# MonitorAndMCUConn.net
KiCad netlist of a schematic drawn in Altium Designer
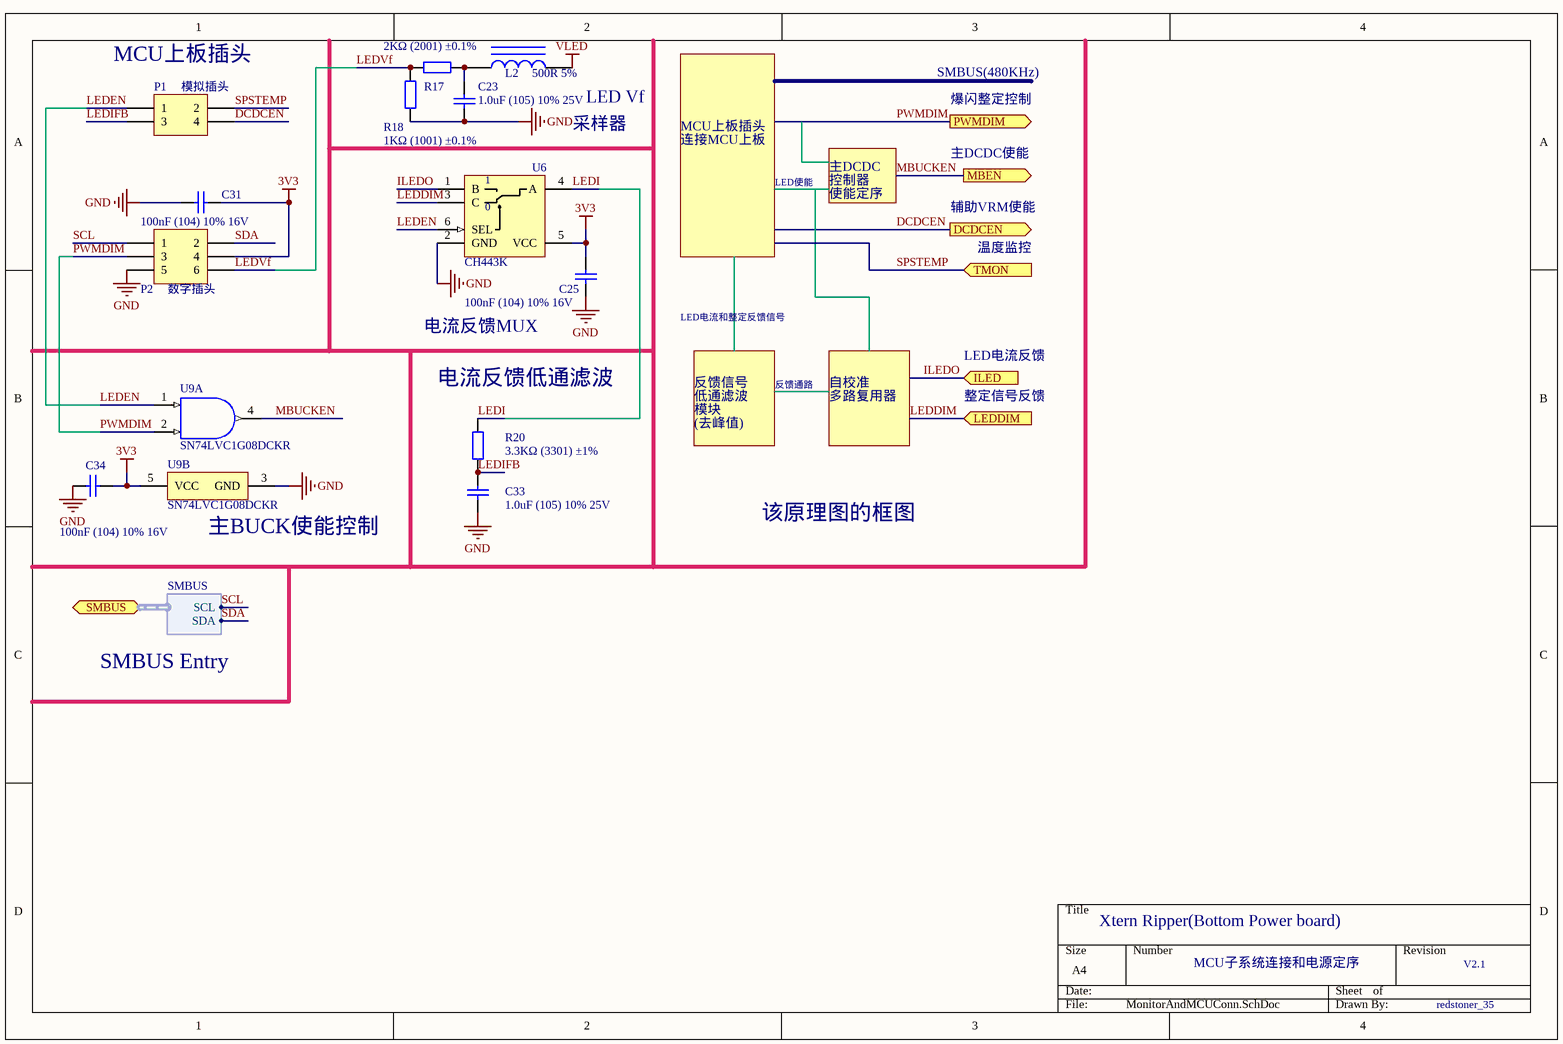
[diagram p0: MonitorAndMCUConn.SchDoc]

(export (version "E")
  (design (tool "Eeschema 10.0.6"))
  (components
    (comp (ref "C23")
      (value "1.0uF (105) 10% 25V")
      (footprint "0402_C")
      (description "贴片电容")
      (libsource (lib "Miscellaneous Devices LC") (part "0402 1.0uF (105) 10% 25V"))
    )
    (comp (ref "C25")
      (value "100nF (104) 10% 16V")
      (footprint "0402_C")
      (description "贴片电容")
      (libsource (lib "Miscellaneous Devices LC") (part "0402 100nF (104) 10% 16V"))
    )
    (comp (ref "C31")
      (value "100nF (104) 10% 16V")
      (footprint "0402_C")
      (description "贴片电容")
      (libsource (lib "Miscellaneous Devices LC") (part "0402 100nF (104) 10% 16V"))
    )
    (comp (ref "C33")
      (value "1.0uF (105) 10% 25V")
      (footprint "0402_C")
      (description "贴片电容")
      (libsource (lib "Miscellaneous Devices LC") (part "0402 1.0uF (105) 10% 25V"))
    )
    (comp (ref "C34")
      (value "100nF (104) 10% 16V")
      (footprint "0402_C")
      (description "贴片电容")
      (libsource (lib "Miscellaneous Devices LC") (part "0402 100nF (104) 10% 16V"))
    )
    (comp (ref "L2")
      (value "500R 5%")
      (footprint "0402_L")
      (description "贴片磁珠")
      (libsource (lib "Miscellaneous Devices LC") (part "0402 27nH 5%"))
    )
    (comp (ref "P1")
      (value "模拟插头")
      (footprint "MHDR2X2")
      (description "Header, 2-Pin, Dual row")
      (fields (field (name "PUBLISHER") "Altium Limited"))
      (libsource (lib "Miscellaneous Connectors") (part "MHDR2X2"))
    )
    (comp (ref "P2")
      (value "数字插头")
      (footprint "MHDR2X3")
      (description "Header, 3-Pin, Dual row")
      (fields (field (name "PUBLISHER") "Altium Limited"))
      (libsource (lib "Miscellaneous Connectors") (part "MHDR2X3"))
    )
    (comp (ref "R17")
      (value "2KΩ (2001) ±0.1%")
      (footprint "0402_R")
      (description "贴片电阻")
      (libsource (lib "Miscellaneous Devices LC") (part "0402 2KΩ (2001) 1%"))
    )
    (comp (ref "R18")
      (value "1KΩ (1001) ±0.1%")
      (footprint "0402_R")
      (description "贴片电阻")
      (libsource (lib "Miscellaneous Devices LC") (part "0402 1KΩ (1001) 1%"))
    )
    (comp (ref "R20")
      (value "3.3KΩ (3301) ±1%")
      (footprint "0402_R")
      (description "贴片电阻")
      (libsource (lib "Miscellaneous Devices LC") (part "0402 3.3KΩ (3301) 1%"))
    )
    (comp (ref "U6")
      (value "CH443K")
      (footprint "SC70-6")
      (description "Low-Voltage Analog Switch SPDT,1.8-5V Power")
      (libsource (lib "custom") (part "NC7SB3157P6X"))
    )
    (comp (ref "U9")
      (value "SN74LVC1G08DCKR")
      (footprint "DCK0005A_N")
      (description "Single 2-Input Positive-AND Gate, DCK0005A, LARGE T&R")
      (fields
        (field (name "GENERIC PART NUMBER") "SN74LVC1G08")
        (field (name "MANUFACTURER") "Texas Instruments")
      )
      (libsource (lib "TI_Logic_Little_Logic") (part "SN74LVC1G08DCKR"))
    )
  )
  (nets
    (net (code "2") (name "/DCDCEN") (class "Default")
      (node (ref "P1") (pin "4") (pinfunction "4_4") (pintype "passive"))
    )
    (net (code "3") (name "/ILEDO") (class "Default")
      (node (ref "U6") (pin "1") (pinfunction "B_1") (pintype "passive"))
    )
    (net (code "4") (name "/LEDDIM") (class "Default")
      (node (ref "U6") (pin "3") (pinfunction "C_3") (pintype "passive"))
    )
    (net (code "5") (name "/LEDEN") (class "Default")
      (node (ref "P1") (pin "1") (pinfunction "1_1") (pintype "passive"))
      (node (ref "U6") (pin "6") (pinfunction "SEL_6") (pintype "input"))
      (node (ref "U9") (pin "1") (pinfunction "A_1") (pintype "input"))
    )
    (net (code "6") (name "/LEDI") (class "Default")
      (node (ref "R20") (pin "2") (pinfunction "2_2") (pintype "passive"))
      (node (ref "U6") (pin "4") (pinfunction "A_4") (pintype "passive"))
    )
    (net (code "7") (name "/LEDIFB") (class "Default")
      (node (ref "C33") (pin "2") (pinfunction "2_2") (pintype "passive"))
      (node (ref "P1") (pin "3") (pinfunction "3_3") (pintype "passive"))
      (node (ref "R20") (pin "1") (pinfunction "1_1") (pintype "passive"))
    )
    (net (code "8") (name "/LEDVf") (class "Default")
      (node (ref "P2") (pin "6") (pinfunction "6_6") (pintype "passive"))
      (node (ref "R17") (pin "2") (pinfunction "2_2") (pintype "passive"))
      (node (ref "R18") (pin "2") (pinfunction "2_2") (pintype "passive"))
    )
    (net (code "9") (name "/MBUCKEN") (class "Default")
      (node (ref "U9") (pin "4") (pinfunction "Y_4") (pintype "output"))
    )
    (net (code "10") (name "/PWMDIM") (class "Default")
      (node (ref "P2") (pin "3") (pinfunction "3_3") (pintype "passive"))
      (node (ref "U9") (pin "2") (pinfunction "B_2") (pintype "input"))
    )
    (net (code "11") (name "/SCL") (class "Default")
      (node (ref "P2") (pin "1") (pinfunction "1_1") (pintype "passive"))
    )
    (net (code "12") (name "/SDA") (class "Default")
      (node (ref "P2") (pin "2") (pinfunction "2_2") (pintype "passive"))
    )
    (net (code "13") (name "/SPSTEMP") (class "Default")
      (node (ref "P1") (pin "2") (pinfunction "2_2") (pintype "passive"))
    )
    (net (code "15") (name "3V3") (class "Default")
      (node (ref "C25") (pin "2") (pinfunction "2_2") (pintype "passive"))
      (node (ref "C31") (pin "2") (pinfunction "2_2") (pintype "passive"))
      (node (ref "C34") (pin "2") (pinfunction "2_2") (pintype "passive"))
      (node (ref "P2") (pin "4") (pinfunction "4_4") (pintype "passive"))
      (node (ref "U6") (pin "5") (pinfunction "VCC_5") (pintype "power_in"))
      (node (ref "U9") (pin "5") (pinfunction "VCC_5") (pintype "power_in"))
    )
    (net (code "16") (name "GND") (class "Default")
      (node (ref "C23") (pin "1") (pinfunction "1_1") (pintype "passive"))
      (node (ref "C25") (pin "1") (pinfunction "1_1") (pintype "passive"))
      (node (ref "C31") (pin "1") (pinfunction "1_1") (pintype "passive"))
      (node (ref "C33") (pin "1") (pinfunction "1_1") (pintype "passive"))
      (node (ref "C34") (pin "1") (pinfunction "1_1") (pintype "passive"))
      (node (ref "P2") (pin "5") (pinfunction "5_5") (pintype "passive"))
      (node (ref "R18") (pin "1") (pinfunction "1_1") (pintype "passive"))
      (node (ref "U6") (pin "2") (pinfunction "GND_2") (pintype "power_in"))
      (node (ref "U9") (pin "3") (pinfunction "GND_3") (pintype "power_in"))
    )
    (net (code "17") (name "Net-(C23-Pad2)") (class "Default")
      (node (ref "C23") (pin "2") (pinfunction "2_2") (pintype "passive"))
      (node (ref "L2") (pin "2") (pinfunction "2_2") (pintype "passive"))
      (node (ref "R17") (pin "1") (pinfunction "1_1") (pintype "passive"))
    )
    (net (code "18") (name "VLED") (class "Default")
      (node (ref "L2") (pin "1") (pinfunction "1_1") (pintype "passive"))
    )
  )
)
